# SCK_DATA_BOARD_2_3.net
KiCad netlist of a schematic drawn in EAGLE
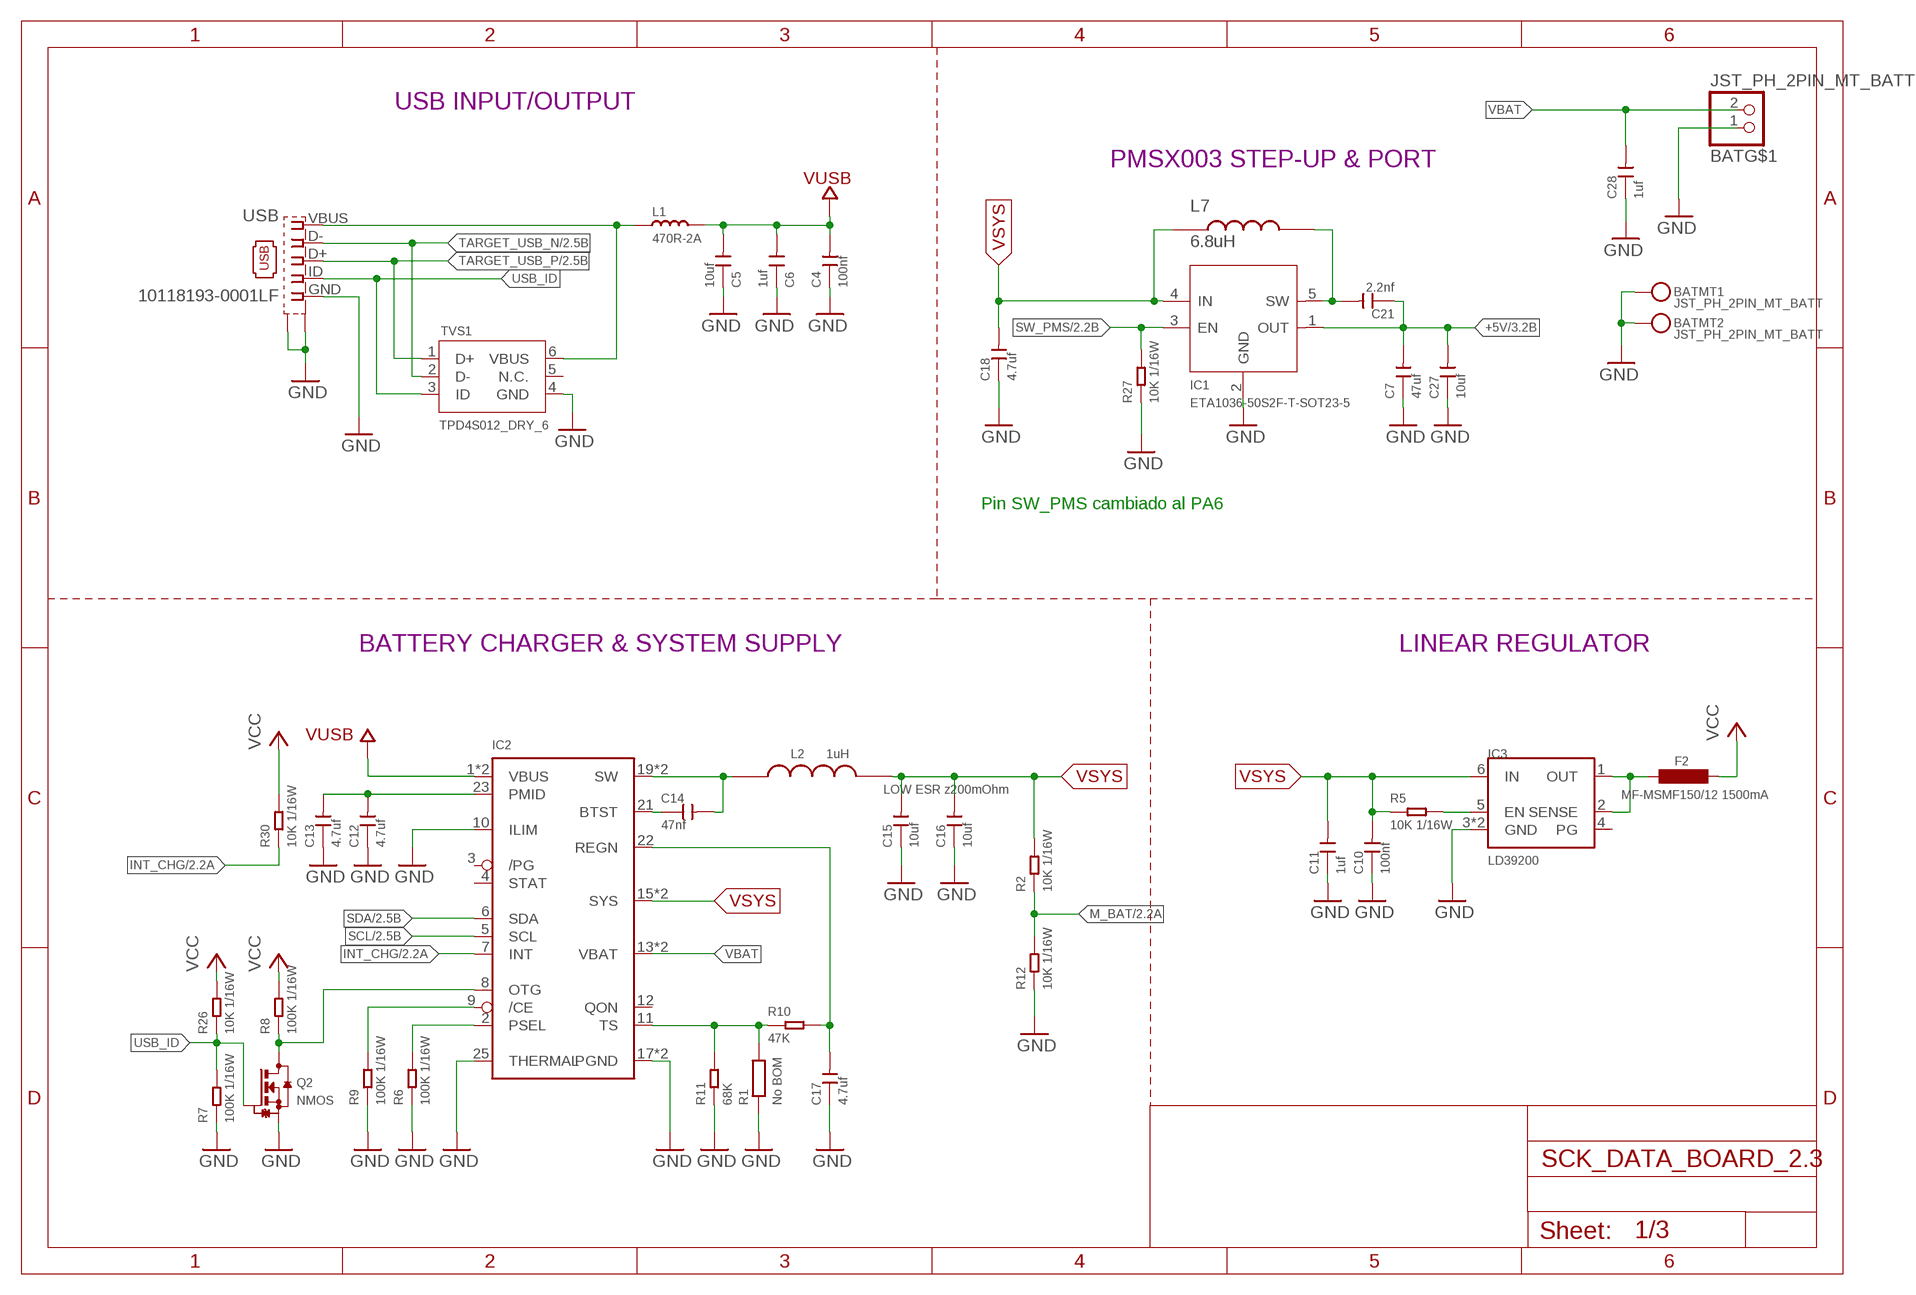
[diagram p0: schematic, sheet 1]
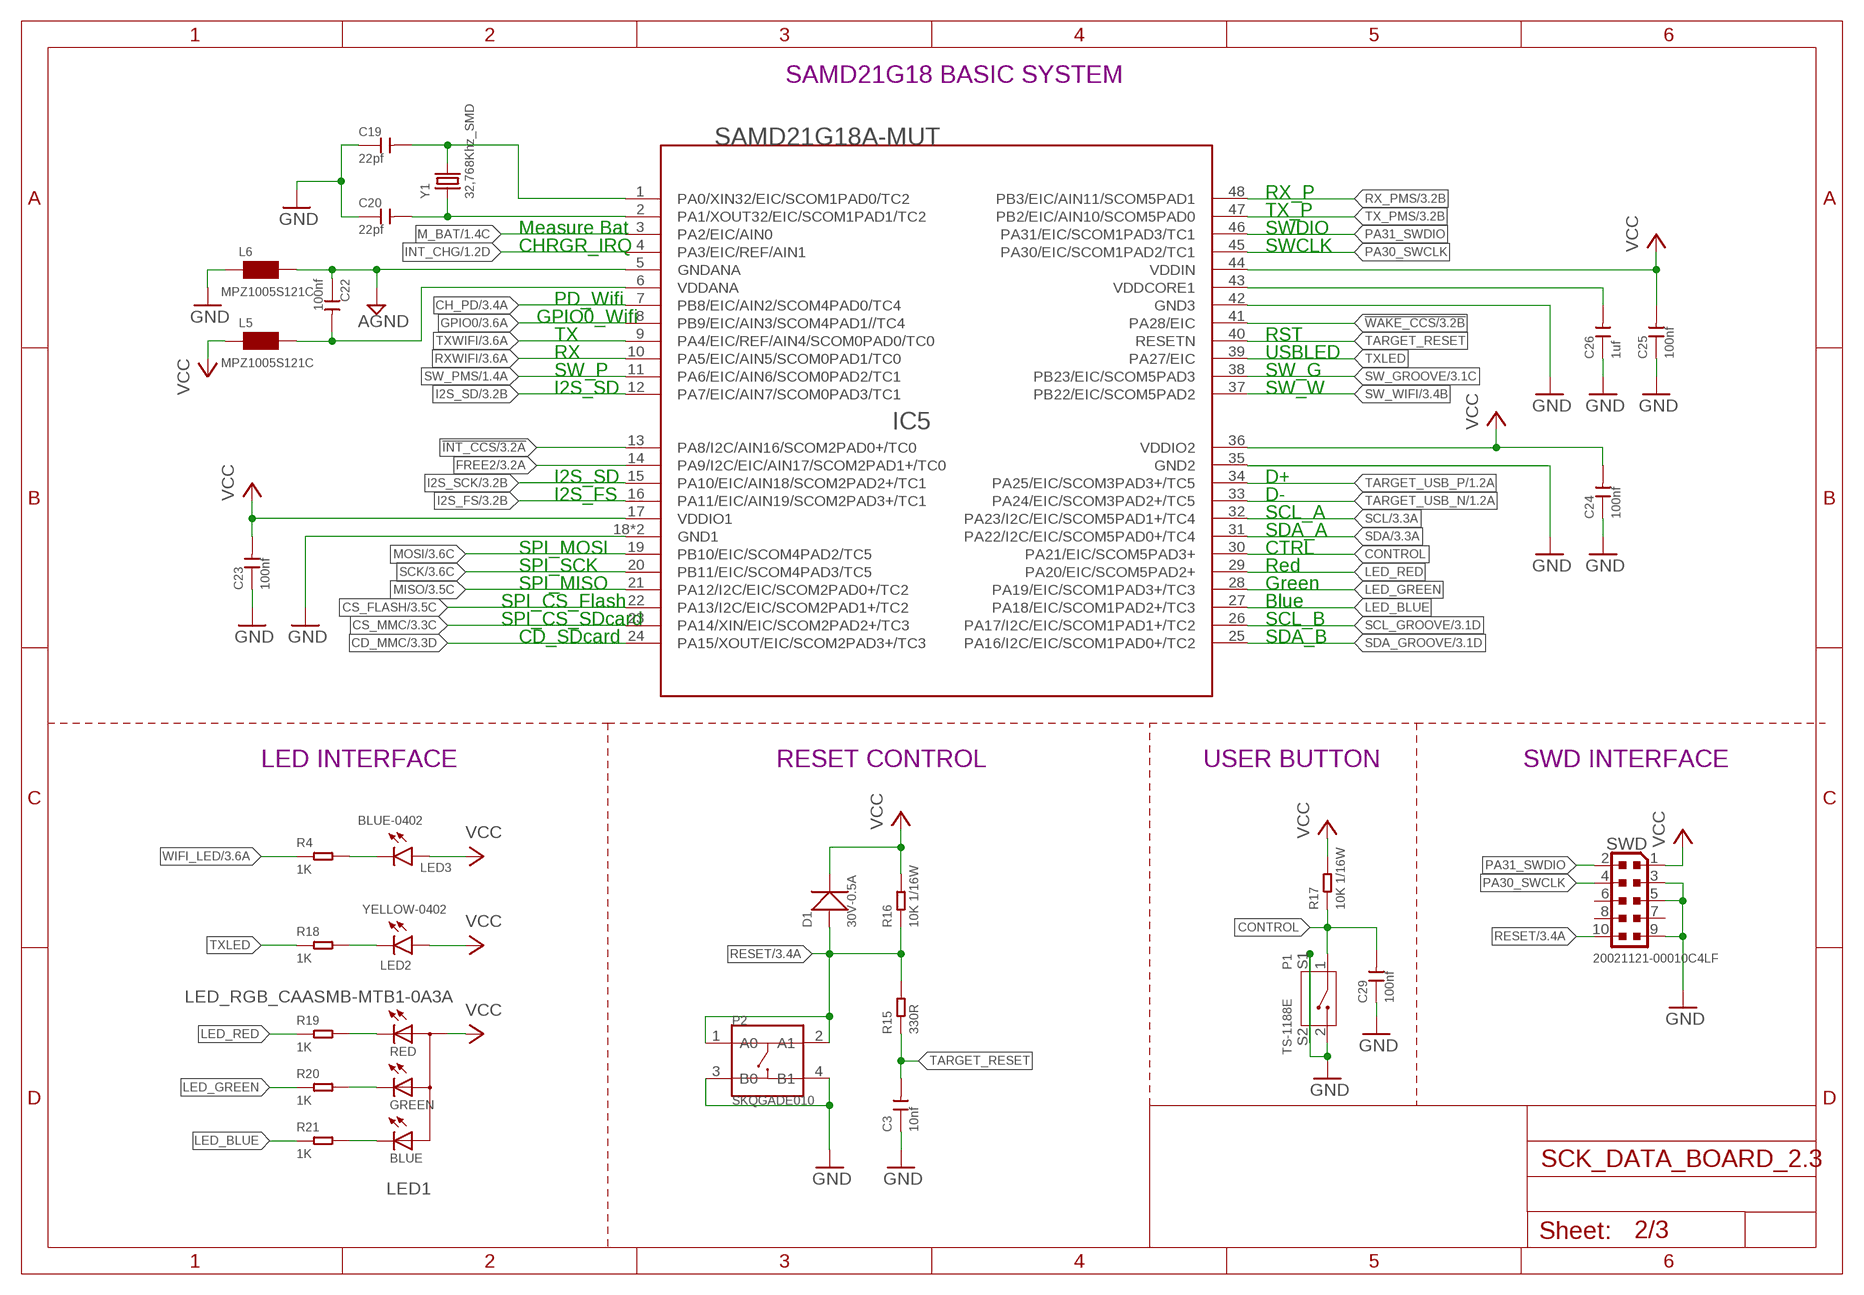
[diagram p1: schematic, sheet 2]
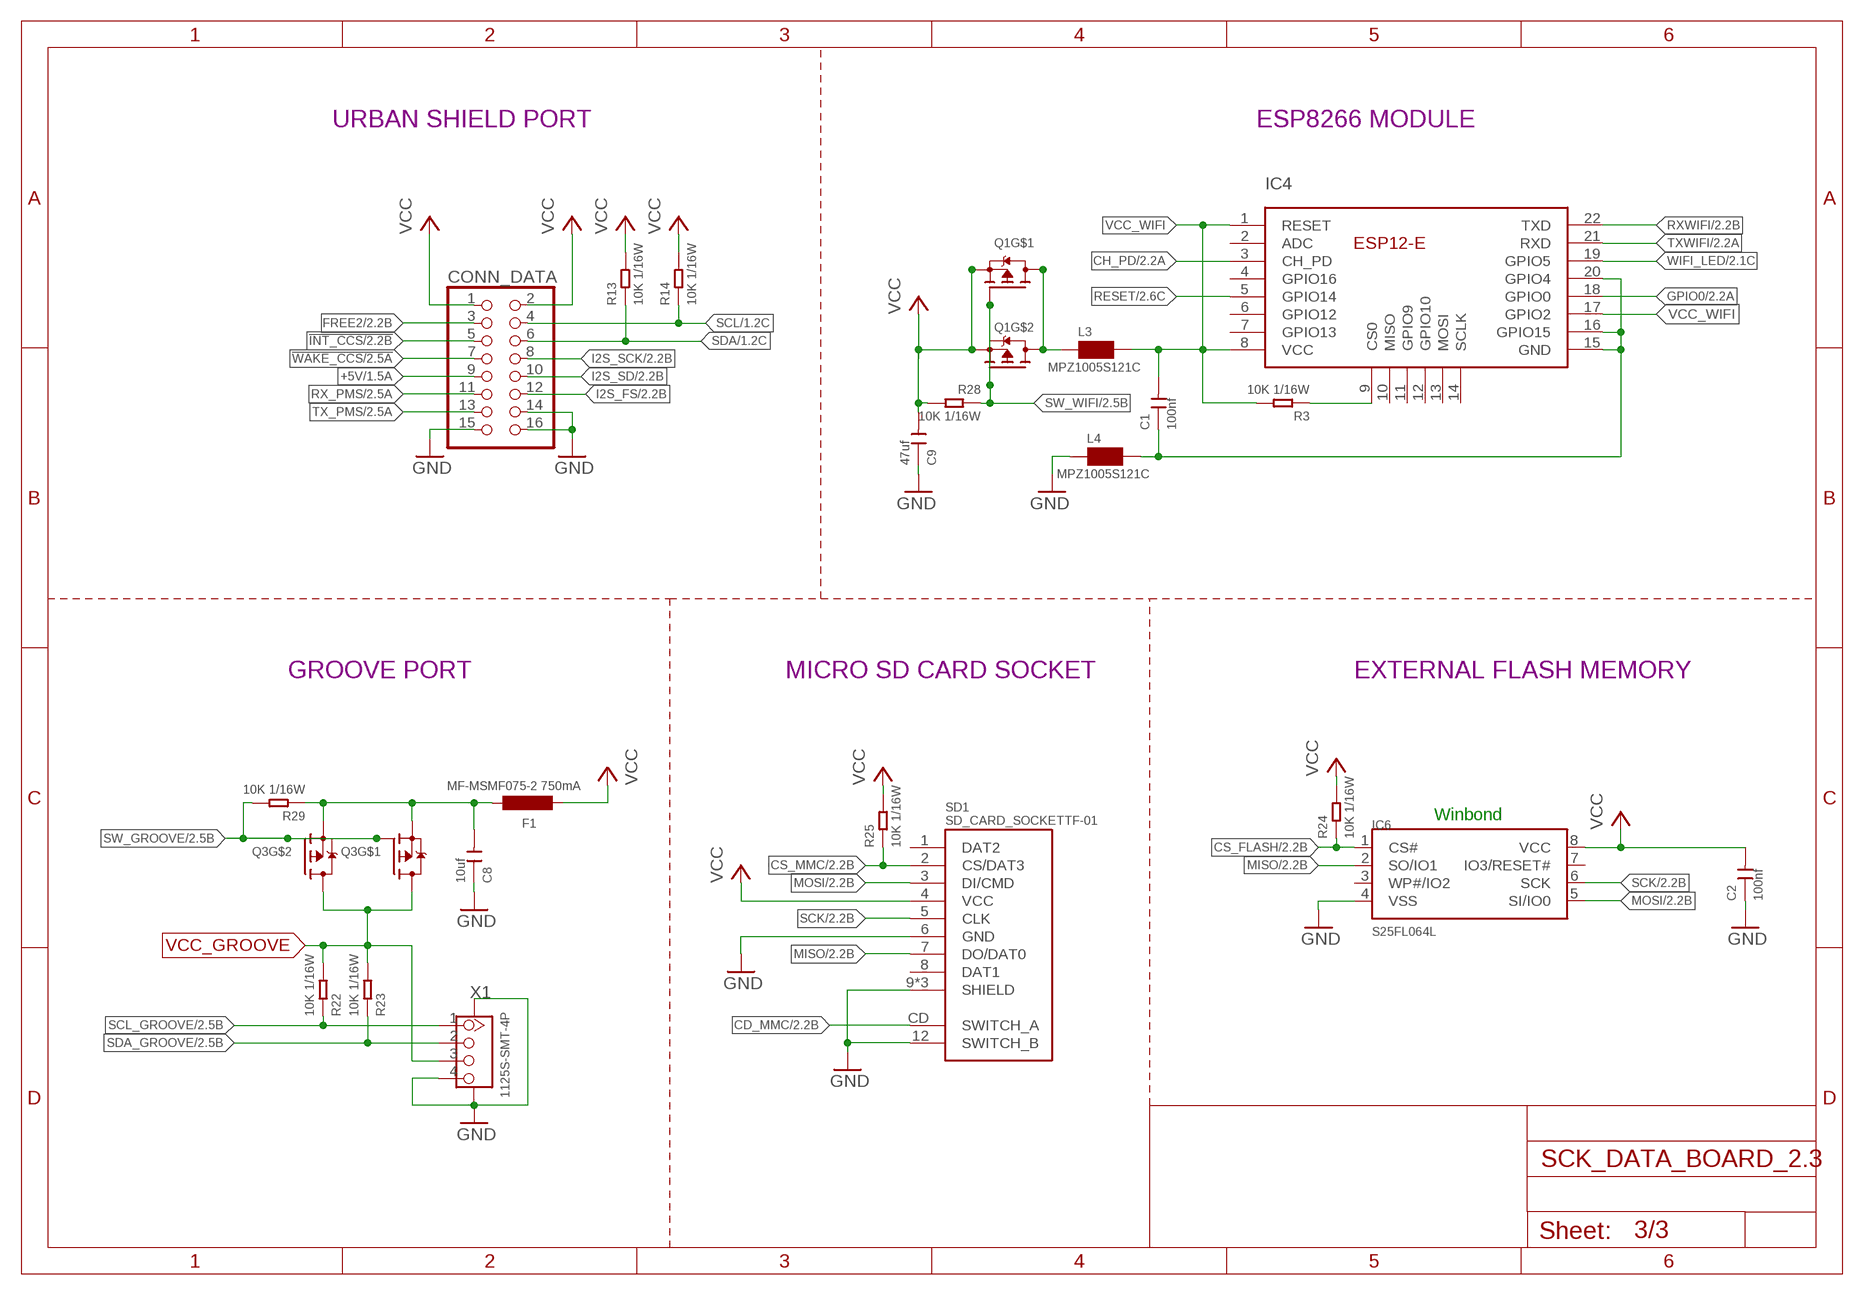
[diagram p2: schematic, sheet 3]

(export (version "E")
  (design (tool "Eeschema 10.0.6"))
  (components
    (comp (ref "C1")
      (value "100nf")
      (footprint "eagle-import:C0402")
      (fields (field (name "MPN") "CC0402KRX7R8BB104"))
      (libsource (lib "eagle-import") (part "CERAMIC-100NF-25V-10%-X7R(0402)"))
    )
    (comp (ref "C2")
      (value "100nf")
      (footprint "eagle-import:C0402")
      (fields (field (name "MPN") "CC0402KRX7R8BB104"))
      (libsource (lib "eagle-import") (part "CERAMIC-100NF-25V-10%-X7R(0402)"))
    )
    (comp (ref "C8")
      (value "10uf")
      (footprint "eagle-import:C1206")
      (fields (field (name "MPN") "CC1206KKX5R8BB106"))
      (libsource (lib "eagle-import") (part "CERAMIC-10UF-25V-10%-X5R(1206)"))
    )
    (comp (ref "C9")
      (value "47uf")
      (footprint "eagle-import:C1210")
      (fields (field (name "MPN") "GRM32ER71A476ME15L"))
      (libsource (lib "eagle-import") (part "CERAMIC-47UF-10V-20%-X7R(1210)"))
    )
    (comp (ref "CONN_DATA")
      (value "PINHD_2X8FEM_SMD")
      (footprint "eagle-import:PINHD_2X8_SMD_FEMALE_UNHOLED")
      (libsource (lib "eagle-import") (part "PINHD_2X8FEM_SMD"))
    )
    (comp (ref "F1")
      (value "MF-MSMF075-2 750mA")
      (footprint "eagle-import:L1812")
      (libsource (lib "eagle-import") (part "L-EUL1812"))
    )
    (comp (ref "IC4")
      (value "HANGAR_ESP-12-E")
      (footprint "eagle-import:HANGAR_ESP12-E")
      (libsource (lib "eagle-import") (part "HANGAR_ESP-12-E"))
    )
    (comp (ref "IC6")
      (value "S25FL064L")
      (footprint "eagle-import:SOIC_8-208MILS")
      (libsource (lib "eagle-import") (part "FLASH_S25FL064L"))
    )
    (comp (ref "L3")
      (value "MPZ1005S121C")
      (footprint "eagle-import:0402")
      (libsource (lib "eagle-import") (part "WE-CBF_0402"))
    )
    (comp (ref "L4")
      (value "MPZ1005S121C")
      (footprint "eagle-import:0402")
      (libsource (lib "eagle-import") (part "WE-CBF_0402"))
    )
    (comp (ref "Q1")
      (value "PMOS")
      (footprint "eagle-import:POWERPAK-SC70-6L")
      (fields (field (name "MPN") "SIA923AEDJ-T1-GE3 "))
      (libsource (lib "eagle-import") (part "MOSFET-PCHANNEL-DUAL"))
    )
    (comp (ref "Q3")
      (value "PMOS")
      (footprint "eagle-import:POWERPAK-SC70-6L")
      (libsource (lib "eagle-import") (part "MOSFET-PCHANNEL-DUAL"))
    )
    (comp (ref "R3")
      (value "10K 1/16W")
      (footprint "eagle-import:R0402")
      (fields (field (name "MPN") "RC0402FR-0710KL"))
      (libsource (lib "eagle-import") (part "SMD-RES-10K-1%-1/16W(0402)"))
    )
    (comp (ref "R13")
      (value "10K 1/16W")
      (footprint "eagle-import:R0402")
      (fields (field (name "MPN") "RC0402FR-0710KL"))
      (libsource (lib "eagle-import") (part "SMD-RES-10K-1%-1/16W(0402)"))
    )
    (comp (ref "R14")
      (value "10K 1/16W")
      (footprint "eagle-import:R0402")
      (fields (field (name "MPN") "RC0402FR-0710KL"))
      (libsource (lib "eagle-import") (part "SMD-RES-10K-1%-1/16W(0402)"))
    )
    (comp (ref "R22")
      (value "10K 1/16W")
      (footprint "eagle-import:R0402")
      (fields (field (name "MPN") "RC0402FR-0710KL"))
      (libsource (lib "eagle-import") (part "SMD-RES-10K-1%-1/16W(0402)"))
    )
    (comp (ref "R23")
      (value "10K 1/16W")
      (footprint "eagle-import:R0402")
      (fields (field (name "MPN") "RC0402FR-0710KL"))
      (libsource (lib "eagle-import") (part "SMD-RES-10K-1%-1/16W(0402)"))
    )
    (comp (ref "R24")
      (value "10K 1/16W")
      (footprint "eagle-import:R0402")
      (fields (field (name "MPN") "RC0402FR-0710KL"))
      (libsource (lib "eagle-import") (part "SMD-RES-10K-1%-1/16W(0402)"))
    )
    (comp (ref "R25")
      (value "10K 1/16W")
      (footprint "eagle-import:R0402")
      (fields (field (name "MPN") "RC0402FR-0710KL"))
      (libsource (lib "eagle-import") (part "SMD-RES-10K-1%-1/16W(0402)"))
    )
    (comp (ref "R28")
      (value "10K 1/16W")
      (footprint "eagle-import:R0402")
      (fields (field (name "MPN") "RC0402FR-0710KL"))
      (libsource (lib "eagle-import") (part "Seeed-Resistor_SMD-RES-10K-1%-1/16W(0402)"))
    )
    (comp (ref "R29")
      (value "10K 1/16W")
      (footprint "eagle-import:R0402")
      (fields (field (name "MPN") "RC0402FR-0710KL"))
      (libsource (lib "eagle-import") (part "Seeed-Resistor_SMD-RES-10K-1%-1/16W(0402)"))
    )
    (comp (ref "SD1")
      (value "SD_CARD_SOCKETTF-01")
      (footprint "eagle-import:TF-01")
      (fields (field (name "MPN") "320090008"))
      (libsource (lib "eagle-import") (part "SD_CARD_SOCKETTF-01"))
    )
    (comp (ref "X1")
      (value "1125S-SMT-4P")
      (footprint "eagle-import:CONNECTOR-NEW_HW4-SMD-2.0")
      (fields (field (name "MPN") "320110030"))
      (libsource (lib "eagle-import") (part "GROVE-CONNECTOR-SMDDD"))
    )
    (comp (ref "BAT")
      (value "JST_PH_2PIN_MT_BATT")
      (footprint "eagle-import:JSTPH2_BATT")
      (libsource (lib "eagle-import") (part "JST_PH_2PIN_MT_BATT"))
    )
    (comp (ref "C4")
      (value "100nf")
      (footprint "eagle-import:C0402")
      (fields (field (name "MPN") "CC0402KRX7R8BB104"))
      (libsource (lib "eagle-import") (part "CERAMIC-100NF-25V-10%-X7R(0402)"))
    )
    (comp (ref "C5")
      (value "10uf")
      (footprint "eagle-import:C1206")
      (fields (field (name "MPN") "CC1206KKX5R8BB106"))
      (libsource (lib "eagle-import") (part "CERAMIC-10UF-25V-10%-X5R(1206)"))
    )
    (comp (ref "C6")
      (value "1uf")
      (footprint "eagle-import:C0805")
      (fields (field (name "MPN") "CC0805KKX7R8BB105"))
      (libsource (lib "eagle-import") (part "CERAMIC-1UF-25V-10%-X7R(0805)"))
    )
    (comp (ref "C7")
      (value "47uf")
      (footprint "eagle-import:C0805")
      (fields (field (name "MPN") "CC0805MKX5R5BB476"))
      (libsource (lib "eagle-import") (part "CERAMIC-47UF-6.3V-20%-X5R(0805)"))
    )
    (comp (ref "C10")
      (value "100nf")
      (footprint "eagle-import:C0402")
      (fields (field (name "MPN") "CC0402KRX7R8BB104"))
      (libsource (lib "eagle-import") (part "CERAMIC-100NF-25V-10%-X7R(0402)"))
    )
    (comp (ref "C11")
      (value "1uf")
      (footprint "eagle-import:C0805")
      (fields (field (name "MPN") "CC0805KKX7R8BB105"))
      (libsource (lib "eagle-import") (part "CERAMIC-1UF-25V-10%-X7R(0805)"))
    )
    (comp (ref "C12")
      (value "4.7uf")
      (footprint "eagle-import:C0603")
      (fields (field (name "MPN") "CC0603KRX5R6BB475"))
      (libsource (lib "eagle-import") (part "CERAMIC-4.7UF-10V-10%-X5R(0603)"))
    )
    (comp (ref "C13")
      (value "4.7uf")
      (footprint "eagle-import:C0603")
      (fields (field (name "MPN") "CC0603KRX5R6BB475"))
      (libsource (lib "eagle-import") (part "CERAMIC-4.7UF-10V-10%-X5R(0603)"))
    )
    (comp (ref "C14")
      (value "47nf")
      (footprint "eagle-import:C0402")
      (fields (field (name "MPN") "CC0402KRX7R8BB473"))
      (libsource (lib "eagle-import") (part "CERAMIC-47NF-25V-10%-X7R(0402)"))
    )
    (comp (ref "C15")
      (value "10uf")
      (footprint "eagle-import:C0603")
      (fields (field (name "MPN") "CC0603KRX5R6BB106"))
      (libsource (lib "eagle-import") (part "Seeed-OPL-Capacitor_CERAMIC-10UF-10V-10%-X5R(0603)"))
    )
    (comp (ref "C16")
      (value "10uf")
      (footprint "eagle-import:C0603")
      (fields (field (name "MPN") "CC0603KRX5R6BB106"))
      (libsource (lib "eagle-import") (part "Seeed-OPL-Capacitor_CERAMIC-10UF-10V-10%-X5R(0603)"))
    )
    (comp (ref "C17")
      (value "4.7uf")
      (footprint "eagle-import:C0603")
      (fields (field (name "MPN") "CC0603KRX5R6BB475"))
      (libsource (lib "eagle-import") (part "CERAMIC-4.7UF-10V-10%-X5R(0603)"))
    )
    (comp (ref "C18")
      (value "4.7uf")
      (footprint "eagle-import:C0603")
      (fields (field (name "MPN") "CC0603KRX5R6BB475"))
      (libsource (lib "eagle-import") (part "CERAMIC-4.7UF-10V-10%-X5R(0603)"))
    )
    (comp (ref "C21")
      (value "2.2nf")
      (footprint "eagle-import:C0402")
      (fields (field (name "MPN") "CC0402KRX7R9BB222"))
      (libsource (lib "eagle-import") (part "CERAMIC-2.2NF-50V-10%-X7R(0402)"))
    )
    (comp (ref "C27")
      (value "10uf")
      (footprint "eagle-import:C0603")
      (fields (field (name "MPN") "CC0603KRX5R6BB106"))
      (libsource (lib "eagle-import") (part "CERAMIC-10UF-10V-10%-X5R(0603)"))
    )
    (comp (ref "C28")
      (value "1uf")
      (footprint "eagle-import:C0805")
      (fields (field (name "MPN") "CC0805KKX7R8BB105"))
      (libsource (lib "eagle-import") (part "CERAMIC-1UF-25V-10%-X7R(0805)"))
    )
    (comp (ref "F2")
      (value "MF-MSMF150/12 1500mA")
      (footprint "eagle-import:L1812")
      (libsource (lib "eagle-import") (part "L-EUL1812"))
    )
    (comp (ref "IC1")
      (value "ETA1036-50S2F-T-SOT23-5")
      (footprint "eagle-import:SOT-23-5")
      (fields (field (name "MPN") "ETA1036-50S2F-T"))
      (libsource (lib "eagle-import") (part "PMIC-ETA1036-50S2F-T(SOT23-5)"))
    )
    (comp (ref "IC2")
      (value "BQ24259_VQFN(24)")
      (footprint "eagle-import:24-PIN_VQFN_THPAD")
      (libsource (lib "eagle-import") (part "BQ24259_VQFN(24)"))
    )
    (comp (ref "IC3")
      (value "LD39200")
      (footprint "eagle-import:DFN6_3X3MM")
      (libsource (lib "eagle-import") (part "LD39200"))
    )
    (comp (ref "L1")
      (value "470R-2A")
      (footprint "eagle-import:L0805")
      (fields (field (name "MPN") "WLB2012-471T20"))
      (libsource (lib "eagle-import") (part "SMD-FERRITE-BEAD-470R-2A(0805)'0805'"))
    )
    (comp (ref "L2")
      (value "1uH")
      (footprint "eagle-import:HANGAR_C1210")
      (libsource (lib "eagle-import") (part "LQH32PN1R0NNCL"))
    )
    (comp (ref "L7")
      (value "6.8uH")
      (footprint "eagle-import:IND_BOURNS_SRN3015TA_3X3_SMD")
      (libsource (lib "eagle-import") (part "RCL_L_SMD_SRN3015TA-6R8M"))
    )
    (comp (ref "Q2")
      (value "NMOS")
      (footprint "eagle-import:NMOS_UMT3")
      (libsource (lib "eagle-import") (part "NMOS_RJU003N03FRAT106"))
    )
    (comp (ref "R1")
      (value "No BOM")
      (footprint "eagle-import:HANGAR_R0402")
      (libsource (lib "eagle-import") (part "HANGAR_R-EU_R0402"))
    )
    (comp (ref "R2")
      (value "10K 1/16W")
      (footprint "eagle-import:R0402")
      (fields (field (name "MPN") "RC0402FR-0710KL"))
      (libsource (lib "eagle-import") (part "SMD-RES-10K-1%-1/16W(0402)"))
    )
    (comp (ref "R5")
      (value "10K 1/16W")
      (footprint "eagle-import:R0402")
      (fields (field (name "MPN") "RC0402FR-0710KL"))
      (libsource (lib "eagle-import") (part "SMD-RES-10K-1%-1/16W(0402)"))
    )
    (comp (ref "R6")
      (value "100K 1/16W")
      (footprint "eagle-import:R0402")
      (fields (field (name "MPN") "RC0402JR-07100KL"))
      (libsource (lib "eagle-import") (part "SMD-RES-100K-5%-1/16W(0402)"))
    )
    (comp (ref "R7")
      (value "100K 1/16W")
      (footprint "eagle-import:R0402")
      (fields (field (name "MPN") "RC0402JR-07100KL"))
      (libsource (lib "eagle-import") (part "SMD-RES-100K-5%-1/16W(0402)"))
    )
    (comp (ref "R8")
      (value "100K 1/16W")
      (footprint "eagle-import:R0402")
      (fields (field (name "MPN") "RC0402JR-07100KL"))
      (libsource (lib "eagle-import") (part "SMD-RES-100K-5%-1/16W(0402)"))
    )
    (comp (ref "R9")
      (value "100K 1/16W")
      (footprint "eagle-import:R0402")
      (fields (field (name "MPN") "RC0402JR-07100KL"))
      (libsource (lib "eagle-import") (part "SMD-RES-100K-5%-1/16W(0402)"))
    )
    (comp (ref "R10")
      (value "47K")
      (footprint "eagle-import:R0402")
      (fields (field (name "MPN") "RC0402JR-0747KL"))
      (libsource (lib "eagle-import") (part "SMD-RES-47K-5%-1/16W(0402)"))
    )
    (comp (ref "R11")
      (value "68K")
      (footprint "eagle-import:R0402")
      (fields (field (name "MPN") "RC0402JR-0768KL"))
      (libsource (lib "eagle-import") (part "SMD-RES-68K-50V-5%(0402)"))
    )
    (comp (ref "R12")
      (value "10K 1/16W")
      (footprint "eagle-import:R0402")
      (fields (field (name "MPN") "RC0402FR-0710KL"))
      (libsource (lib "eagle-import") (part "SMD-RES-10K-1%-1/16W(0402)"))
    )
    (comp (ref "R26")
      (value "10K 1/16W")
      (footprint "eagle-import:R0402")
      (fields (field (name "MPN") "RC0402FR-0710KL"))
      (libsource (lib "eagle-import") (part "SMD-RES-10K-1%-1/16W(0402)"))
    )
    (comp (ref "R27")
      (value "10K 1/16W")
      (footprint "eagle-import:R0402")
      (fields (field (name "MPN") "RC0402FR-0710KL"))
      (libsource (lib "eagle-import") (part "Seeed-Resistor_SMD-RES-10K-1%-1/16W(0402)"))
    )
    (comp (ref "R30")
      (value "10K 1/16W")
      (footprint "eagle-import:R0402")
      (fields (field (name "MPN") "RC0402FR-0710KL"))
      (libsource (lib "eagle-import") (part "SMD-RES-10K-1%-1/16W(0402)"))
    )
    (comp (ref "TVS1")
      (value "TPD4S012_DRY_6")
      (footprint "eagle-import:DRY6")
      (libsource (lib "eagle-import") (part "TPD4S012_DRY_6"))
    )
    (comp (ref "USB")
      (value "10118193-0001LF")
      (footprint "eagle-import:CON2_USB_MICRO_B_AT")
      (libsource (lib "eagle-import") (part "USB_MICRO_USB"))
    )
    (comp (ref "C3")
      (value "10nf")
      (footprint "eagle-import:C0402")
      (fields (field (name "MPN") "CC0402KRX7R9BB103"))
      (libsource (lib "eagle-import") (part "CERAMIC-10NF-50V-10%-X7R(0402)"))
    )
    (comp (ref "C19")
      (value "22pf")
      (footprint "eagle-import:C0402")
      (fields (field (name "MPN") "CC0402JRNPO9BN220"))
      (libsource (lib "eagle-import") (part "CERAMIC-22PF-50V-5%-NPO(0402)"))
    )
    (comp (ref "C20")
      (value "22pf")
      (footprint "eagle-import:C0402")
      (fields (field (name "MPN") "CC0402JRNPO9BN220"))
      (libsource (lib "eagle-import") (part "CERAMIC-22PF-50V-5%-NPO(0402)"))
    )
    (comp (ref "C22")
      (value "100nf")
      (footprint "eagle-import:C0402")
      (fields (field (name "MPN") "CC0402KRX7R8BB104"))
      (libsource (lib "eagle-import") (part "CERAMIC-100NF-25V-10%-X7R(0402)"))
    )
    (comp (ref "C23")
      (value "100nf")
      (footprint "eagle-import:C0402")
      (fields (field (name "MPN") "CC0402KRX7R8BB104"))
      (libsource (lib "eagle-import") (part "CERAMIC-100NF-25V-10%-X7R(0402)"))
    )
    (comp (ref "C24")
      (value "100nf")
      (footprint "eagle-import:C0402")
      (fields (field (name "MPN") "CC0402KRX7R8BB104"))
      (libsource (lib "eagle-import") (part "CERAMIC-100NF-25V-10%-X7R(0402)"))
    )
    (comp (ref "C25")
      (value "100nf")
      (footprint "eagle-import:C0402")
      (fields (field (name "MPN") "CC0402KRX7R8BB104"))
      (libsource (lib "eagle-import") (part "CERAMIC-100NF-25V-10%-X7R(0402)"))
    )
    (comp (ref "C26")
      (value "1uf")
      (footprint "eagle-import:C0805")
      (fields (field (name "MPN") "CC0805KKX7R8BB105"))
      (libsource (lib "eagle-import") (part "CERAMIC-1UF-25V-10%-X7R(0805)"))
    )
    (comp (ref "C29")
      (value "100nf")
      (footprint "eagle-import:C0402")
      (fields (field (name "MPN") "CC0402KRX7R8BB104"))
      (libsource (lib "eagle-import") (part "CERAMIC-100NF-25V-10%-X7R(0402)"))
    )
    (comp (ref "D1")
      (value "30V-0.5A")
      (footprint "eagle-import:SOD-323")
      (fields (field (name "MPN") "LRB551V-30T1G"))
      (libsource (lib "eagle-import") (part "SMD-DIODE-SCHOTTKY-30V-0.5A(SOD-323)"))
    )
    (comp (ref "IC5")
      (value "SAMD21G18A-MUT")
      (footprint "eagle-import:QFN48-7X7")
      (libsource (lib "eagle-import") (part "SAMD21G18A-MUT"))
    )
    (comp (ref "L5")
      (value "MPZ1005S121C")
      (footprint "eagle-import:0402")
      (libsource (lib "eagle-import") (part "WE-CBF_0402"))
    )
    (comp (ref "L6")
      (value "MPZ1005S121C")
      (footprint "eagle-import:0402")
      (libsource (lib "eagle-import") (part "WE-CBF_0402"))
    )
    (comp (ref "LED1")
      (value "LED_RGB_CAASMB-MTB1-0A3A")
      (footprint "eagle-import:HANGAR_P-LCC-4")
      (libsource (lib "eagle-import") (part "LED_RGB_CAASMB-MTB1-0A3A"))
    )
    (comp (ref "LED2")
      (value "YELLOW-0402")
      (footprint "eagle-import:CHIPLED_0402_YELLOW")
      (libsource (lib "eagle-import") (part "Hangar3D_37241589_LEDCHIPLED_0402_YELLOW"))
    )
    (comp (ref "LED3")
      (value "BLUE-0402")
      (footprint "eagle-import:CHIPLED_0402_BLUE")
      (libsource (lib "eagle-import") (part "LEDCHIPLED_0402_BLUE"))
    )
    (comp (ref "P1")
      (value "TS-1188E")
      (footprint "eagle-import:SW4-SMD-7.0X3.5X3.5MM-90D")
      (libsource (lib "eagle-import") (part "SMD-BUTTON(2+2P-7X3.5MM-90D)"))
    )
    (comp (ref "P2")
      (value "SKQGADE010")
      (footprint "eagle-import:SW4-SMD-5.2X5.2X1.5MM")
      (libsource (lib "eagle-import") (part "SKQGADE010-SKQGADE010"))
    )
    (comp (ref "R4")
      (value "1K")
      (footprint "eagle-import:R0402")
      (fields (field (name "MPN") "RC0402JR-071KL"))
      (libsource (lib "eagle-import") (part "SMD-RES-1K-5%-1/16W(0402)"))
    )
    (comp (ref "R15")
      (value "330R")
      (footprint "eagle-import:R0402")
      (fields (field (name "MPN") "RC0402FR-07330RL"))
      (libsource (lib "eagle-import") (part "SMD-RES-330R-1%-1/16W(0402)"))
    )
    (comp (ref "R16")
      (value "10K 1/16W")
      (footprint "eagle-import:R0402")
      (fields (field (name "MPN") "RC0402FR-0710KL"))
      (libsource (lib "eagle-import") (part "SMD-RES-10K-1%-1/16W(0402)"))
    )
    (comp (ref "R17")
      (value "10K 1/16W")
      (footprint "eagle-import:R0402")
      (fields (field (name "MPN") "RC0402FR-0710KL"))
      (libsource (lib "eagle-import") (part "SMD-RES-10K-1%-1/16W(0402)"))
    )
    (comp (ref "R18")
      (value "1K")
      (footprint "eagle-import:R0402")
      (fields (field (name "MPN") "RC0402JR-071KL"))
      (libsource (lib "eagle-import") (part "SMD-RES-1K-5%-1/16W(0402)"))
    )
    (comp (ref "R19")
      (value "1K")
      (footprint "eagle-import:R0402")
      (fields (field (name "MPN") "RC0402JR-071KL"))
      (libsource (lib "eagle-import") (part "SMD-RES-1K-5%-1/16W(0402)"))
    )
    (comp (ref "R20")
      (value "1K")
      (footprint "eagle-import:R0402")
      (fields (field (name "MPN") "RC0402JR-071KL"))
      (libsource (lib "eagle-import") (part "SMD-RES-1K-5%-1/16W(0402)"))
    )
    (comp (ref "R21")
      (value "1K")
      (footprint "eagle-import:R0402")
      (fields (field (name "MPN") "RC0402JR-071KL"))
      (libsource (lib "eagle-import") (part "SMD-RES-1K-5%-1/16W(0402)"))
    )
    (comp (ref "SWD")
      (value "20021121-00010C4LF")
      (footprint "eagle-import:2X05_SMD_1.27MM")
      (libsource (lib "eagle-import") (part "PINHEAD_PINHD-2X5SMD"))
    )
    (comp (ref "Y1")
      (value "32,768Khz_SMD")
      (footprint "eagle-import:CRISTALLI_RESONATOR_EPSON_FC_145")
      (fields (field (name "PART_NUMBER") "ABS07-32.768KHZ-T"))
      (libsource (lib "eagle-import") (part "CRISTALLI_0213_ABS07-32.768KHZ-T"))
    )
  )
  (nets
    (net (code "1") (name "+5V") (class "Default")
      (node (ref "C21") (pin "1") (pinfunction "1_1") (pintype "passive"))
      (node (ref "C27") (pin "2") (pinfunction "2_2") (pintype "passive"))
      (node (ref "C7") (pin "2") (pinfunction "2_2") (pintype "passive"))
      (node (ref "CONN_DATA") (pin "9") (pinfunction "9_9") (pintype "passive"))
      (node (ref "IC1") (pin "1") (pinfunction "OUT_1") (pintype "bidirectional"))
    )
    (net (code "2") (name "AGND") (class "Default")
      (node (ref "C22") (pin "1") (pinfunction "1_1") (pintype "passive"))
      (node (ref "IC5") (pin "5") (pinfunction "GNDANA_5") (pintype "power_in"))
      (node (ref "L6") (pin "2") (pinfunction "2_2") (pintype "passive"))
    )
    (net (code "3") (name "CD_MMC") (class "Default")
      (node (ref "IC5") (pin "24") (pinfunction "PA15/XOUT/EIC/SCOM2PAD3+/TC3_24") (pintype "bidirectional"))
      (node (ref "SD1") (pin "CD") (pinfunction "SWITCH_A_CD") (pintype "bidirectional"))
    )
    (net (code "4") (name "CH_PD") (class "Default")
      (node (ref "IC4") (pin "3") (pinfunction "CH_PD_3") (pintype "input"))
      (node (ref "IC5") (pin "7") (pinfunction "PB8/EIC/AIN2/SCOM4PAD0/TC4_7") (pintype "bidirectional"))
    )
    (net (code "5") (name "CONTROL") (class "Default")
      (node (ref "C29") (pin "2") (pinfunction "2_2") (pintype "passive"))
      (node (ref "IC5") (pin "30") (pinfunction "PA21/EIC/SCOM5PAD3+_30") (pintype "bidirectional"))
      (node (ref "P1") (pin "1") (pinfunction "1_1") (pintype "bidirectional"))
      (node (ref "R17") (pin "1") (pinfunction "1_1") (pintype "passive"))
    )
    (net (code "6") (name "CS_FLASH") (class "Default")
      (node (ref "IC5") (pin "22") (pinfunction "PA13/I2C/EIC/SCOM2PAD1+/TC2_22") (pintype "bidirectional"))
      (node (ref "IC6") (pin "1") (pinfunction "CS#_1") (pintype "bidirectional"))
      (node (ref "R24") (pin "1") (pinfunction "1_1") (pintype "passive"))
    )
    (net (code "7") (name "CS_MMC") (class "Default")
      (node (ref "IC5") (pin "23") (pinfunction "PA14/XIN/EIC/SCOM2PAD2+/TC3_23") (pintype "bidirectional"))
      (node (ref "R25") (pin "1") (pinfunction "1_1") (pintype "passive"))
      (node (ref "SD1") (pin "2") (pinfunction "CS/DAT3_2") (pintype "bidirectional"))
    )
    (net (code "8") (name "FREE2") (class "Default")
      (node (ref "CONN_DATA") (pin "3") (pinfunction "3_3") (pintype "passive"))
      (node (ref "IC5") (pin "14") (pinfunction "PA9/I2C/EIC/AIN17/SCOM2PAD1+/TC0_14") (pintype "bidirectional"))
    )
    (net (code "9") (name "GND") (class "Default")
      (node (ref "BAT") (pin "1") (pinfunction "1_1") (pintype "passive"))
      (node (ref "BAT") (pin "NC1") (pinfunction "P$1_NC1") (pintype "bidirectional"))
      (node (ref "BAT") (pin "NC2") (pinfunction "P$1_NC2") (pintype "bidirectional"))
      (node (ref "C10") (pin "1") (pinfunction "1_1") (pintype "passive"))
      (node (ref "C11") (pin "1") (pinfunction "1_1") (pintype "passive"))
      (node (ref "C12") (pin "1") (pinfunction "1_1") (pintype "passive"))
      (node (ref "C13") (pin "1") (pinfunction "1_1") (pintype "passive"))
      (node (ref "C15") (pin "1") (pinfunction "1_1") (pintype "passive"))
      (node (ref "C16") (pin "1") (pinfunction "1_1") (pintype "passive"))
      (node (ref "C17") (pin "1") (pinfunction "1_1") (pintype "passive"))
      (node (ref "C18") (pin "1") (pinfunction "1_1") (pintype "passive"))
      (node (ref "C19") (pin "1") (pinfunction "1_1") (pintype "passive"))
      (node (ref "C2") (pin "1") (pinfunction "1_1") (pintype "passive"))
      (node (ref "C20") (pin "1") (pinfunction "1_1") (pintype "passive"))
      (node (ref "C23") (pin "1") (pinfunction "1_1") (pintype "passive"))
      (node (ref "C24") (pin "1") (pinfunction "1_1") (pintype "passive"))
      (node (ref "C25") (pin "1") (pinfunction "1_1") (pintype "passive"))
      (node (ref "C26") (pin "1") (pinfunction "1_1") (pintype "passive"))
      (node (ref "C27") (pin "1") (pinfunction "1_1") (pintype "passive"))
      (node (ref "C28") (pin "1") (pinfunction "1_1") (pintype "passive"))
      (node (ref "C29") (pin "1") (pinfunction "1_1") (pintype "passive"))
      (node (ref "C3") (pin "1") (pinfunction "1_1") (pintype "passive"))
      (node (ref "C4") (pin "1") (pinfunction "1_1") (pintype "passive"))
      (node (ref "C5") (pin "1") (pinfunction "1_1") (pintype "passive"))
      (node (ref "C6") (pin "1") (pinfunction "1_1") (pintype "passive"))
      (node (ref "C7") (pin "1") (pinfunction "1_1") (pintype "passive"))
      (node (ref "C8") (pin "1") (pinfunction "1_1") (pintype "passive"))
      (node (ref "C9") (pin "1") (pinfunction "1_1") (pintype "passive"))
      (node (ref "CONN_DATA") (pin "14") (pinfunction "14_14") (pintype "passive"))
      (node (ref "CONN_DATA") (pin "15") (pinfunction "15_15") (pintype "passive"))
      (node (ref "CONN_DATA") (pin "16") (pinfunction "16_16") (pintype "passive"))
      (node (ref "IC1") (pin "2") (pinfunction "GND_2") (pintype "bidirectional"))
      (node (ref "IC2") (pin "10") (pinfunction "ILIM_10") (pintype "bidirectional"))
      (node (ref "IC2") (pin "17") (pinfunction "PGND_17") (pintype "bidirectional"))
      (node (ref "IC2") (pin "18") (pinfunction "PGND_18") (pintype "bidirectional"))
      (node (ref "IC2") (pin "25") (pinfunction "THERMAL_25") (pintype "bidirectional"))
      (node (ref "IC3") (pin "3") (pinfunction "GND_3") (pintype "bidirectional"))
      (node (ref "IC3") (pin "7") (pinfunction "GND_7") (pintype "bidirectional"))
      (node (ref "IC5") (pin "18") (pinfunction "GND1_18") (pintype "power_in"))
      (node (ref "IC5") (pin "35") (pinfunction "GND2_35") (pintype "power_in"))
      (node (ref "IC5") (pin "42") (pinfunction "GND3_42") (pintype "power_in"))
      (node (ref "IC5") (pin "TP") (pinfunction "GND1_TP") (pintype "power_in"))
      (node (ref "IC6") (pin "4") (pinfunction "VSS_4") (pintype "bidirectional"))
      (node (ref "L4") (pin "2") (pinfunction "2_2") (pintype "passive"))
      (node (ref "L6") (pin "1") (pinfunction "1_1") (pintype "passive"))
      (node (ref "P1") (pin "2") (pinfunction "2_2") (pintype "bidirectional"))
      (node (ref "P1") (pin "S1") (pinfunction "S1_S1") (pintype "bidirectional"))
      (node (ref "P1") (pin "S2") (pinfunction "S2_S2") (pintype "bidirectional"))
      (node (ref "P2") (pin "3") (pinfunction "B0_3") (pintype "bidirectional"))
      (node (ref "P2") (pin "4") (pinfunction "B1_4") (pintype "bidirectional"))
      (node (ref "Q2") (pin "1") (pinfunction "S_1") (pintype "passive"))
      (node (ref "R1") (pin "1") (pinfunction "1_1") (pintype "passive"))
      (node (ref "R11") (pin "1") (pinfunction "1_1") (pintype "passive"))
      (node (ref "R12") (pin "1") (pinfunction "1_1") (pintype "passive"))
      (node (ref "R27") (pin "1") (pinfunction "1_1") (pintype "passive"))
      (node (ref "R6") (pin "1") (pinfunction "1_1") (pintype "passive"))
      (node (ref "R7") (pin "1") (pinfunction "1_1") (pintype "passive"))
      (node (ref "R9") (pin "1") (pinfunction "1_1") (pintype "passive"))
      (node (ref "SD1") (pin "10") (pinfunction "SHIELD_10") (pintype "bidirectional"))
      (node (ref "SD1") (pin "11") (pinfunction "SHIELD_11") (pintype "bidirectional"))
      (node (ref "SD1") (pin "12") (pinfunction "SWITCH_B_12") (pintype "bidirectional"))
      (node (ref "SD1") (pin "6") (pinfunction "GND_6") (pintype "bidirectional"))
      (node (ref "SD1") (pin "9") (pinfunction "SHIELD_9") (pintype "bidirectional"))
      (node (ref "SWD") (pin "3") (pinfunction "3_3") (pintype "passive"))
      (node (ref "SWD") (pin "5") (pinfunction "5_5") (pintype "passive"))
      (node (ref "SWD") (pin "9") (pinfunction "9_9") (pintype "passive"))
      (node (ref "TVS1") (pin "4") (pinfunction "GND_4") (pintype "passive"))
      (node (ref "USB") (pin "GND") (pinfunction "5_GND") (pintype "passive"))
      (node (ref "USB") (pin "P$1") (pinfunction "S1_P$1") (pintype "passive"))
      (node (ref "USB") (pin "P$2") (pinfunction "S1_P$2") (pintype "passive"))
      (node (ref "USB") (pin "P$3") (pinfunction "S1_P$3") (pintype "passive"))
      (node (ref "USB") (pin "P$4") (pinfunction "S1_P$4") (pintype "passive"))
      (node (ref "USB") (pin "P$5") (pinfunction "S1_P$5") (pintype "passive"))
      (node (ref "USB") (pin "P$6") (pinfunction "S1_P$6") (pintype "passive"))
      (node (ref "USB") (pin "P$7") (pinfunction "S1_P$7") (pintype "passive"))
      (node (ref "USB") (pin "P$8") (pinfunction "S1_P$8") (pintype "passive"))
      (node (ref "USB") (pin "S1") (pinfunction "S2_S1") (pintype "passive"))
      (node (ref "USB") (pin "S2") (pinfunction "S2_S2") (pintype "passive"))
      (node (ref "USB") (pin "S3") (pinfunction "S2_S3") (pintype "passive"))
      (node (ref "USB") (pin "S4") (pinfunction "S2_S4") (pintype "passive"))
      (node (ref "USB") (pin "S5") (pinfunction "S2_S5") (pintype "passive"))
      (node (ref "USB") (pin "S6") (pinfunction "S2_S6") (pintype "passive"))
      (node (ref "X1") (pin "4") (pinfunction "4_4") (pintype "bidirectional"))
      (node (ref "X1") (pin "SS1") (pinfunction "SS1_SS1") (pintype "bidirectional"))
      (node (ref "X1") (pin "SS2") (pinfunction "SS2_SS2") (pintype "bidirectional"))
    )
    (net (code "10") (name "GPIO0") (class "Default")
      (node (ref "IC4") (pin "18") (pinfunction "GPIO0_18") (pintype "bidirectional"))
      (node (ref "IC5") (pin "8") (pinfunction "PB9/EIC/AIN3/SCOM4PAD1//TC4_8") (pintype "bidirectional"))
    )
    (net (code "11") (name "I2S_FS") (class "Default")
      (node (ref "CONN_DATA") (pin "12") (pinfunction "12_12") (pintype "passive"))
      (node (ref "IC5") (pin "16") (pinfunction "PA11/EIC/AIN19/SCOM2PAD3+/TC1_16") (pintype "bidirectional"))
    )
    (net (code "12") (name "I2S_SCK") (class "Default")
      (node (ref "CONN_DATA") (pin "8") (pinfunction "8_8") (pintype "passive"))
      (node (ref "IC5") (pin "15") (pinfunction "PA10/EIC/AIN18/SCOM2PAD2+/TC1_15") (pintype "bidirectional"))
    )
    (net (code "13") (name "I2S_SD") (class "Default")
      (node (ref "CONN_DATA") (pin "10") (pinfunction "10_10") (pintype "passive"))
      (node (ref "IC5") (pin "12") (pinfunction "PA7/EIC/AIN7/SCOM0PAD3/TC1_12") (pintype "bidirectional"))
    )
    (net (code "14") (name "INT_CHG") (class "Default")
      (node (ref "IC2") (pin "7") (pinfunction "INT_7") (pintype "bidirectional"))
      (node (ref "IC5") (pin "4") (pinfunction "PA3/EIC/REF/AIN1_4") (pintype "bidirectional"))
      (node (ref "R30") (pin "1") (pinfunction "1_1") (pintype "passive"))
    )
    (net (code "15") (name "LED_BLUE") (class "Default")
      (node (ref "IC5") (pin "27") (pinfunction "PA18/EIC/SCOM1PAD2+/TC3_27") (pintype "bidirectional"))
      (node (ref "R21") (pin "1") (pinfunction "1_1") (pintype "passive"))
    )
    (net (code "16") (name "LED_GREEN") (class "Default")
      (node (ref "IC5") (pin "28") (pinfunction "PA19/EIC/SCOM1PAD3+/TC3_28") (pintype "bidirectional"))
      (node (ref "R20") (pin "1") (pinfunction "1_1") (pintype "passive"))
    )
    (net (code "17") (name "LED_RED") (class "Default")
      (node (ref "IC5") (pin "29") (pinfunction "PA20/EIC/SCOM5PAD2+_29") (pintype "bidirectional"))
      (node (ref "R19") (pin "1") (pinfunction "1_1") (pintype "passive"))
    )
    (net (code "18") (name "MISO") (class "Default")
      (node (ref "IC5") (pin "21") (pinfunction "PA12/I2C/EIC/SCOM2PAD0+/TC2_21") (pintype "bidirectional"))
      (node (ref "IC6") (pin "2") (pinfunction "SO/IO1_2") (pintype "bidirectional"))
      (node (ref "SD1") (pin "7") (pinfunction "DO/DAT0_7") (pintype "bidirectional"))
    )
    (net (code "19") (name "MOSI") (class "Default")
      (node (ref "IC5") (pin "19") (pinfunction "PB10/EIC/SCOM4PAD2/TC5_19") (pintype "bidirectional"))
      (node (ref "IC6") (pin "5") (pinfunction "SI/IO0_5") (pintype "bidirectional"))
      (node (ref "SD1") (pin "3") (pinfunction "DI/CMD_3") (pintype "bidirectional"))
    )
    (net (code "20") (name "M_BAT") (class "Default")
      (node (ref "IC5") (pin "3") (pinfunction "PA2/EIC/AIN0_3") (pintype "bidirectional"))
      (node (ref "R12") (pin "2") (pinfunction "2_2") (pintype "passive"))
      (node (ref "R2") (pin "1") (pinfunction "1_1") (pintype "passive"))
    )
    (net (code "21") (name "Net-(C14-Pad2)") (class "Default")
      (node (ref "C14") (pin "2") (pinfunction "2_2") (pintype "passive"))
      (node (ref "IC2") (pin "19") (pinfunction "SW_19") (pintype "bidirectional"))
      (node (ref "IC2") (pin "20") (pinfunction "SW_20") (pintype "bidirectional"))
      (node (ref "L2") (pin "1") (pinfunction "1_1") (pintype "bidirectional"))
    )
    (net (code "22") (name "Net-(IC1-SW)") (class "Default")
      (node (ref "C21") (pin "2") (pinfunction "2_2") (pintype "passive"))
      (node (ref "IC1") (pin "5") (pinfunction "SW_5") (pintype "bidirectional"))
      (node (ref "L7") (pin "P$2") (pinfunction "P$2_P$2") (pintype "bidirectional"))
    )
    (net (code "23") (name "Net-(IC2-BTST)") (class "Default")
      (node (ref "C14") (pin "1") (pinfunction "1_1") (pintype "passive"))
      (node (ref "IC2") (pin "21") (pinfunction "BTST_21") (pintype "bidirectional"))
    )
    (net (code "24") (name "Net-(IC2-OTG)") (class "Default")
      (node (ref "IC2") (pin "8") (pinfunction "OTG_8") (pintype "bidirectional"))
      (node (ref "Q2") (pin "3") (pinfunction "D_3") (pintype "passive"))
      (node (ref "R8") (pin "1") (pinfunction "1_1") (pintype "passive"))
    )
    (net (code "25") (name "Net-(IC2-PMID)") (class "Default")
      (node (ref "C12") (pin "2") (pinfunction "2_2") (pintype "passive"))
      (node (ref "C13") (pin "2") (pinfunction "2_2") (pintype "passive"))
      (node (ref "IC2") (pin "23") (pinfunction "PMID_23") (pintype "bidirectional"))
    )
    (net (code "26") (name "Net-(IC2-PSEL)") (class "Default")
      (node (ref "IC2") (pin "2") (pinfunction "PSEL_2") (pintype "bidirectional"))
      (node (ref "R6") (pin "2") (pinfunction "2_2") (pintype "passive"))
    )
    (net (code "27") (name "Net-(IC2-REGN)") (class "Default")
      (node (ref "C17") (pin "2") (pinfunction "2_2") (pintype "passive"))
      (node (ref "IC2") (pin "22") (pinfunction "REGN_22") (pintype "bidirectional"))
      (node (ref "R10") (pin "2") (pinfunction "2_2") (pintype "passive"))
    )
    (net (code "28") (name "Net-(IC2-TS)") (class "Default")
      (node (ref "IC2") (pin "11") (pinfunction "TS_11") (pintype "bidirectional"))
      (node (ref "R1") (pin "2") (pinfunction "2_2") (pintype "passive"))
      (node (ref "R10") (pin "1") (pinfunction "1_1") (pintype "passive"))
      (node (ref "R11") (pin "2") (pinfunction "2_2") (pintype "passive"))
    )
    (net (code "29") (name "Net-(IC2-{slash}CE)") (class "Default")
      (node (ref "IC2") (pin "9") (pinfunction "/CE_9") (pintype "bidirectional"))
      (node (ref "R9") (pin "2") (pinfunction "2_2") (pintype "passive"))
    )
    (net (code "30") (name "Net-(IC3-EN)") (class "Default")
      (node (ref "IC3") (pin "5") (pinfunction "EN_5") (pintype "bidirectional"))
      (node (ref "R5") (pin "2") (pinfunction "2_2") (pintype "passive"))
    )
    (net (code "31") (name "Net-(IC3-OUT)") (class "Default")
      (node (ref "F2") (pin "2") (pinfunction "2_2") (pintype "passive"))
      (node (ref "IC3") (pin "1") (pinfunction "OUT_1") (pintype "bidirectional"))
      (node (ref "IC3") (pin "2") (pinfunction "SENSE_2") (pintype "bidirectional"))
    )
    (net (code "32") (name "Net-(IC4-CS0)") (class "Default")
      (node (ref "IC4") (pin "9") (pinfunction "CS0_9") (pintype "input"))
      (node (ref "R3") (pin "1") (pinfunction "1_1") (pintype "passive"))
    )
    (net (code "33") (name "Net-(IC4-GND)") (class "Default")
      (node (ref "C1") (pin "1") (pinfunction "1_1") (pintype "passive"))
      (node (ref "IC4") (pin "15") (pinfunction "GND_15") (pintype "power_in"))
      (node (ref "IC4") (pin "16") (pinfunction "GPIO15_16") (pintype "bidirectional"))
      (node (ref "IC4") (pin "20") (pinfunction "GPIO4_20") (pintype "bidirectional"))
      (node (ref "L4") (pin "1") (pinfunction "1_1") (pintype "passive"))
    )
    (net (code "34") (name "Net-(IC5-PA0{slash}XIN32{slash}EIC{slash}SCOM1PAD0{slash}TC2)") (class "Default")
      (node (ref "C19") (pin "2") (pinfunction "2_2") (pintype "passive"))
      (node (ref "IC5") (pin "1") (pinfunction "PA0/XIN32/EIC/SCOM1PAD0/TC2_1") (pintype "bidirectional"))
      (node (ref "Y1") (pin "P$2") (pinfunction "2_P$2") (pintype "bidirectional"))
    )
    (net (code "35") (name "Net-(IC5-PA1{slash}XOUT32{slash}EIC{slash}SCOM1PAD1{slash}TC2)") (class "Default")
      (node (ref "C20") (pin "2") (pinfunction "2_2") (pintype "passive"))
      (node (ref "IC5") (pin "2") (pinfunction "PA1/XOUT32/EIC/SCOM1PAD1/TC2_2") (pintype "bidirectional"))
      (node (ref "Y1") (pin "P$1") (pinfunction "1_P$1") (pintype "bidirectional"))
    )
    (net (code "36") (name "Net-(IC5-VDDANA)") (class "Default")
      (node (ref "C22") (pin "2") (pinfunction "2_2") (pintype "passive"))
      (node (ref "IC5") (pin "6") (pinfunction "VDDANA_6") (pintype "power_in"))
      (node (ref "L5") (pin "2") (pinfunction "2_2") (pintype "passive"))
    )
    (net (code "37") (name "Net-(IC5-VDDCORE1)") (class "Default")
      (node (ref "C26") (pin "2") (pinfunction "2_2") (pintype "passive"))
      (node (ref "IC5") (pin "43") (pinfunction "VDDCORE1_43") (pintype "input"))
    )
    (net (code "38") (name "Net-(L3-Pad2)") (class "Default")
      (node (ref "L3") (pin "2") (pinfunction "2_2") (pintype "passive"))
      (node (ref "Q1") (pin "3") (pinfunction "D_3") (pintype "passive"))
      (node (ref "Q1") (pin "6") (pinfunction "D_6") (pintype "passive"))
      (node (ref "Q1") (pin "TP1") (pinfunction "D_TP1") (pintype "passive"))
      (node (ref "Q1") (pin "TP2") (pinfunction "D_TP2") (pintype "passive"))
    )
    (net (code "39") (name "Net-(LED1-BLUE)") (class "Default")
      (node (ref "LED1") (pin "3") (pinfunction "BLUE_3") (pintype "passive"))
      (node (ref "R21") (pin "2") (pinfunction "2_2") (pintype "passive"))
    )
    (net (code "40") (name "Net-(LED1-GREEN)") (class "Default")
      (node (ref "LED1") (pin "2") (pinfunction "GREEN_2") (pintype "passive"))
      (node (ref "R20") (pin "2") (pinfunction "2_2") (pintype "passive"))
    )
    (net (code "41") (name "Net-(LED1-RED)") (class "Default")
      (node (ref "LED1") (pin "1") (pinfunction "RED_1") (pintype "passive"))
      (node (ref "R19") (pin "2") (pinfunction "2_2") (pintype "passive"))
    )
    (net (code "42") (name "Net-(LED2-C)") (class "Default")
      (node (ref "LED2") (pin "K") (pinfunction "C_K") (pintype "passive"))
      (node (ref "R18") (pin "2") (pinfunction "2_2") (pintype "passive"))
    )
    (net (code "43") (name "Net-(LED3-C)") (class "Default")
      (node (ref "LED3") (pin "K") (pinfunction "C_K") (pintype "passive"))
      (node (ref "R4") (pin "2") (pinfunction "2_2") (pintype "passive"))
    )
    (net (code "44") (name "Net-(Q3A-S)") (class "Default")
      (node (ref "C8") (pin "2") (pinfunction "2_2") (pintype "passive"))
      (node (ref "F1") (pin "1") (pinfunction "1_1") (pintype "passive"))
      (node (ref "Q3") (pin "1") (pinfunction "S_1") (pintype "passive"))
      (node (ref "Q3") (pin "4") (pinfunction "S_4") (pintype "passive"))
      (node (ref "R29") (pin "1") (pinfunction "1_1") (pintype "passive"))
    )
    (net (code "45") (name "Net-(TVS1-VBUS)") (class "Default")
      (node (ref "L1") (pin "1") (pinfunction "1_1") (pintype "passive"))
      (node (ref "TVS1") (pin "6") (pinfunction "VBUS_6") (pintype "passive"))
      (node (ref "USB") (pin "VBUS") (pinfunction "1_VBUS") (pintype "passive"))
    )
    (net (code "46") (name "PA30_SWCLK") (class "Default")
      (node (ref "IC5") (pin "45") (pinfunction "PA30/EIC/SCOM1PAD2/TC1_45") (pintype "bidirectional"))
      (node (ref "SWD") (pin "4") (pinfunction "4_4") (pintype "passive"))
    )
    (net (code "47") (name "PA31_SWDIO") (class "Default")
      (node (ref "IC5") (pin "46") (pinfunction "PA31/EIC/SCOM1PAD3/TC1_46") (pintype "bidirectional"))
      (node (ref "SWD") (pin "2") (pinfunction "2_2") (pintype "passive"))
    )
    (net (code "48") (name "RESET") (class "Default")
      (node (ref "D1") (pin "+") (pinfunction "+_+") (pintype "passive"))
      (node (ref "IC4") (pin "5") (pinfunction "GPIO14_5") (pintype "bidirectional"))
      (node (ref "P2") (pin "1") (pinfunction "A0_1") (pintype "bidirectional"))
      (node (ref "P2") (pin "2") (pinfunction "A1_2") (pintype "bidirectional"))
      (node (ref "R15") (pin "2") (pinfunction "2_2") (pintype "passive"))
      (node (ref "R16") (pin "1") (pinfunction "1_1") (pintype "passive"))
      (node (ref "SWD") (pin "10") (pinfunction "10_10") (pintype "passive"))
    )
    (net (code "49") (name "RXWIFI") (class "Default")
      (node (ref "IC4") (pin "22") (pinfunction "TXD_22") (pintype "output"))
      (node (ref "IC5") (pin "10") (pinfunction "PA5/EIC/AIN5/SCOM0PAD1/TC0_10") (pintype "bidirectional"))
    )
    (net (code "50") (name "RX_PMS") (class "Default")
      (node (ref "CONN_DATA") (pin "11") (pinfunction "11_11") (pintype "passive"))
      (node (ref "IC5") (pin "48") (pinfunction "PB3/EIC/AIN11/SCOM5PAD1_48") (pintype "bidirectional"))
    )
    (net (code "51") (name "SCK") (class "Default")
      (node (ref "IC5") (pin "20") (pinfunction "PB11/EIC/SCOM4PAD3/TC5_20") (pintype "bidirectional"))
      (node (ref "IC6") (pin "6") (pinfunction "SCK_6") (pintype "bidirectional"))
      (node (ref "SD1") (pin "5") (pinfunction "CLK_5") (pintype "bidirectional"))
    )
    (net (code "52") (name "SCL") (class "Default")
      (node (ref "CONN_DATA") (pin "4") (pinfunction "4_4") (pintype "passive"))
      (node (ref "IC2") (pin "5") (pinfunction "SCL_5") (pintype "bidirectional"))
      (node (ref "IC5") (pin "32") (pinfunction "PA23/I2C/EIC/SCOM5PAD1+/TC4_32") (pintype "bidirectional"))
      (node (ref "R14") (pin "1") (pinfunction "1_1") (pintype "passive"))
    )
    (net (code "53") (name "SCL_GROOVE") (class "Default")
      (node (ref "IC5") (pin "26") (pinfunction "PA17/I2C/EIC/SCOM1PAD1+/TC2_26") (pintype "bidirectional"))
      (node (ref "R22") (pin "1") (pinfunction "1_1") (pintype "passive"))
      (node (ref "X1") (pin "1") (pinfunction "1_1") (pintype "bidirectional"))
    )
    (net (code "54") (name "SDA") (class "Default")
      (node (ref "CONN_DATA") (pin "6") (pinfunction "6_6") (pintype "passive"))
      (node (ref "IC2") (pin "6") (pinfunction "SDA_6") (pintype "bidirectional"))
      (node (ref "IC5") (pin "31") (pinfunction "PA22/I2C/EIC/SCOM5PAD0+/TC4_31") (pintype "bidirectional"))
      (node (ref "R13") (pin "1") (pinfunction "1_1") (pintype "passive"))
    )
    (net (code "55") (name "SDA_GROOVE") (class "Default")
      (node (ref "IC5") (pin "25") (pinfunction "PA16/I2C/EIC/SCOM1PAD0+/TC2_25") (pintype "bidirectional"))
      (node (ref "R23") (pin "1") (pinfunction "1_1") (pintype "passive"))
      (node (ref "X1") (pin "2") (pinfunction "2_2") (pintype "bidirectional"))
    )
    (net (code "56") (name "SW_GROOVE") (class "Default")
      (node (ref "IC5") (pin "38") (pinfunction "PB23/EIC/SCOM5PAD3_38") (pintype "bidirectional"))
      (node (ref "Q3") (pin "2") (pinfunction "G_2") (pintype "passive"))
      (node (ref "Q3") (pin "5") (pinfunction "G_5") (pintype "passive"))
      (node (ref "R29") (pin "2") (pinfunction "2_2") (pintype "passive"))
    )
    (net (code "57") (name "SW_PMS") (class "Default")
      (node (ref "IC1") (pin "3") (pinfunction "EN_3") (pintype "bidirectional"))
      (node (ref "IC5") (pin "11") (pinfunction "PA6/EIC/AIN6/SCOM0PAD2/TC1_11") (pintype "bidirectional"))
      (node (ref "R27") (pin "2") (pinfunction "2_2") (pintype "passive"))
    )
    (net (code "58") (name "SW_WIFI") (class "Default")
      (node (ref "IC5") (pin "37") (pinfunction "PB22/EIC/SCOM5PAD2_37") (pintype "bidirectional"))
      (node (ref "Q1") (pin "2") (pinfunction "G_2") (pintype "passive"))
      (node (ref "Q1") (pin "5") (pinfunction "G_5") (pintype "passive"))
      (node (ref "R28") (pin "1") (pinfunction "1_1") (pintype "passive"))
    )
    (net (code "59") (name "TARGET_RESET") (class "Default")
      (node (ref "C3") (pin "2") (pinfunction "2_2") (pintype "passive"))
      (node (ref "IC5") (pin "40") (pinfunction "RESETN_40") (pintype "bidirectional"))
      (node (ref "R15") (pin "1") (pinfunction "1_1") (pintype "passive"))
    )
    (net (code "60") (name "TARGET_USB_N") (class "Default")
      (node (ref "IC5") (pin "33") (pinfunction "PA24/EIC/SCOM3PAD2+/TC5_33") (pintype "bidirectional"))
      (node (ref "TVS1") (pin "2") (pinfunction "D-_2") (pintype "passive"))
      (node (ref "USB") (pin "D-") (pinfunction "2_D-") (pintype "passive"))
    )
    (net (code "61") (name "TARGET_USB_P") (class "Default")
      (node (ref "IC5") (pin "34") (pinfunction "PA25/EIC/SCOM3PAD3+/TC5_34") (pintype "bidirectional"))
      (node (ref "TVS1") (pin "1") (pinfunction "D+_1") (pintype "passive"))
      (node (ref "USB") (pin "D+") (pinfunction "3_D+") (pintype "passive"))
    )
    (net (code "62") (name "TXLED") (class "Default")
      (node (ref "IC5") (pin "39") (pinfunction "PA27/EIC_39") (pintype "bidirectional"))
      (node (ref "R18") (pin "1") (pinfunction "1_1") (pintype "passive"))
    )
    (net (code "63") (name "TXWIFI") (class "Default")
      (node (ref "IC4") (pin "21") (pinfunction "RXD_21") (pintype "input"))
      (node (ref "IC5") (pin "9") (pinfunction "PA4/EIC/REF/AIN4/SCOM0PAD0/TC0_9") (pintype "bidirectional"))
    )
    (net (code "64") (name "TX_PMS") (class "Default")
      (node (ref "CONN_DATA") (pin "13") (pinfunction "13_13") (pintype "passive"))
      (node (ref "IC5") (pin "47") (pinfunction "PB2/EIC/AIN10/SCOM5PAD0_47") (pintype "bidirectional"))
    )
    (net (code "65") (name "USB_ID") (class "Default")
      (node (ref "Q2") (pin "2") (pinfunction "G_2") (pintype "passive"))
      (node (ref "R26") (pin "1") (pinfunction "1_1") (pintype "passive"))
      (node (ref "R7") (pin "2") (pinfunction "2_2") (pintype "passive"))
      (node (ref "TVS1") (pin "3") (pinfunction "ID_3") (pintype "passive"))
      (node (ref "USB") (pin "ID") (pinfunction "4_ID") (pintype "passive"))
    )
    (net (code "66") (name "VBAT") (class "Default")
      (node (ref "BAT") (pin "2") (pinfunction "2_2") (pintype "passive"))
      (node (ref "C28") (pin "2") (pinfunction "2_2") (pintype "passive"))
      (node (ref "IC2") (pin "13") (pinfunction "VBAT_13") (pintype "bidirectional"))
      (node (ref "IC2") (pin "14") (pinfunction "VBAT_14") (pintype "bidirectional"))
    )
    (net (code "67") (name "VCC") (class "Default")
      (node (ref "C2") (pin "2") (pinfunction "2_2") (pintype "passive"))
      (node (ref "C23") (pin "2") (pinfunction "2_2") (pintype "passive"))
      (node (ref "C24") (pin "2") (pinfunction "2_2") (pintype "passive"))
      (node (ref "C25") (pin "2") (pinfunction "2_2") (pintype "passive"))
      (node (ref "C9") (pin "2") (pinfunction "2_2") (pintype "passive"))
      (node (ref "CONN_DATA") (pin "1") (pinfunction "1_1") (pintype "passive"))
      (node (ref "CONN_DATA") (pin "2") (pinfunction "2_2") (pintype "passive"))
      (node (ref "D1") (pin "-") (pinfunction "-_-") (pintype "passive"))
      (node (ref "F1") (pin "2") (pinfunction "2_2") (pintype "passive"))
      (node (ref "F2") (pin "1") (pinfunction "1_1") (pintype "passive"))
      (node (ref "IC5") (pin "17") (pinfunction "VDDIO1_17") (pintype "power_in"))
      (node (ref "IC5") (pin "36") (pinfunction "VDDIO2_36") (pintype "power_in"))
      (node (ref "IC5") (pin "44") (pinfunction "VDDIN_44") (pintype "power_in"))
      (node (ref "IC6") (pin "8") (pinfunction "VCC_8") (pintype "bidirectional"))
      (node (ref "L5") (pin "1") (pinfunction "1_1") (pintype "passive"))
      (node (ref "LED1") (pin "4") (pinfunction "A_4") (pintype "passive"))
      (node (ref "LED2") (pin "A") (pinfunction "A_A") (pintype "passive"))
      (node (ref "LED3") (pin "A") (pinfunction "A_A") (pintype "passive"))
      (node (ref "Q1") (pin "1") (pinfunction "S_1") (pintype "passive"))
      (node (ref "Q1") (pin "4") (pinfunction "S_4") (pintype "passive"))
      (node (ref "R13") (pin "2") (pinfunction "2_2") (pintype "passive"))
      (node (ref "R14") (pin "2") (pinfunction "2_2") (pintype "passive"))
      (node (ref "R16") (pin "2") (pinfunction "2_2") (pintype "passive"))
      (node (ref "R17") (pin "2") (pinfunction "2_2") (pintype "passive"))
      (node (ref "R24") (pin "2") (pinfunction "2_2") (pintype "passive"))
      (node (ref "R25") (pin "2") (pinfunction "2_2") (pintype "passive"))
      (node (ref "R26") (pin "2") (pinfunction "2_2") (pintype "passive"))
      (node (ref "R28") (pin "2") (pinfunction "2_2") (pintype "passive"))
      (node (ref "R30") (pin "2") (pinfunction "2_2") (pintype "passive"))
      (node (ref "R8") (pin "2") (pinfunction "2_2") (pintype "passive"))
      (node (ref "SD1") (pin "4") (pinfunction "VCC_4") (pintype "bidirectional"))
      (node (ref "SWD") (pin "1") (pinfunction "1_1") (pintype "passive"))
    )
    (net (code "68") (name "VCC_GROOVE") (class "Default")
      (node (ref "Q3") (pin "3") (pinfunction "D_3") (pintype "passive"))
      (node (ref "Q3") (pin "6") (pinfunction "D_6") (pintype "passive"))
      (node (ref "Q3") (pin "TP1") (pinfunction "D_TP1") (pintype "passive"))
      (node (ref "Q3") (pin "TP2") (pinfunction "D_TP2") (pintype "passive"))
      (node (ref "R22") (pin "2") (pinfunction "2_2") (pintype "passive"))
      (node (ref "R23") (pin "2") (pinfunction "2_2") (pintype "passive"))
      (node (ref "X1") (pin "3") (pinfunction "3_3") (pintype "bidirectional"))
    )
    (net (code "69") (name "VCC_WIFI") (class "Default")
      (node (ref "C1") (pin "2") (pinfunction "2_2") (pintype "passive"))
      (node (ref "IC4") (pin "1") (pinfunction "RESET_1") (pintype "input"))
      (node (ref "IC4") (pin "17") (pinfunction "GPIO2_17") (pintype "bidirectional"))
      (node (ref "IC4") (pin "8") (pinfunction "VCC_8") (pintype "power_in"))
      (node (ref "L3") (pin "1") (pinfunction "1_1") (pintype "passive"))
      (node (ref "R3") (pin "2") (pinfunction "2_2") (pintype "passive"))
    )
    (net (code "70") (name "VSYS") (class "Default")
      (node (ref "C10") (pin "2") (pinfunction "2_2") (pintype "passive"))
      (node (ref "C11") (pin "2") (pinfunction "2_2") (pintype "passive"))
      (node (ref "C15") (pin "2") (pinfunction "2_2") (pintype "passive"))
      (node (ref "C16") (pin "2") (pinfunction "2_2") (pintype "passive"))
      (node (ref "C18") (pin "2") (pinfunction "2_2") (pintype "passive"))
      (node (ref "IC1") (pin "4") (pinfunction "IN_4") (pintype "bidirectional"))
      (node (ref "IC2") (pin "15") (pinfunction "SYS_15") (pintype "bidirectional"))
      (node (ref "IC2") (pin "16") (pinfunction "SYS_16") (pintype "bidirectional"))
      (node (ref "IC3") (pin "6") (pinfunction "IN_6") (pintype "bidirectional"))
      (node (ref "L2") (pin "2") (pinfunction "2_2") (pintype "bidirectional"))
      (node (ref "L7") (pin "P$1") (pinfunction "P$1_P$1") (pintype "bidirectional"))
      (node (ref "R2") (pin "2") (pinfunction "2_2") (pintype "passive"))
      (node (ref "R5") (pin "1") (pinfunction "1_1") (pintype "passive"))
    )
    (net (code "71") (name "VUSB") (class "Default")
      (node (ref "C4") (pin "2") (pinfunction "2_2") (pintype "passive"))
      (node (ref "C5") (pin "2") (pinfunction "2_2") (pintype "passive"))
      (node (ref "C6") (pin "2") (pinfunction "2_2") (pintype "passive"))
      (node (ref "IC2") (pin "1") (pinfunction "VBUS_1") (pintype "bidirectional"))
      (node (ref "IC2") (pin "24") (pinfunction "VBUS_24") (pintype "bidirectional"))
      (node (ref "L1") (pin "2") (pinfunction "2_2") (pintype "passive"))
    )
    (net (code "72") (name "WIFI_LED") (class "Default")
      (node (ref "IC4") (pin "19") (pinfunction "GPIO5_19") (pintype "bidirectional"))
      (node (ref "R4") (pin "1") (pinfunction "1_1") (pintype "passive"))
    )
    (net (code "73") (name "unconnected-(IC2-QON-Pad12)") (class "Default")
      (node (ref "IC2") (pin "12") (pinfunction "QON_12") (pintype "bidirectional"))
    )
    (net (code "74") (name "unconnected-(IC2-STAT-Pad4)") (class "Default")
      (node (ref "IC2") (pin "4") (pinfunction "STAT_4") (pintype "bidirectional"))
    )
    (net (code "75") (name "unconnected-(IC2-{slash}PG-Pad3)") (class "Default")
      (node (ref "IC2") (pin "3") (pinfunction "/PG_3") (pintype "bidirectional"))
    )
    (net (code "76") (name "unconnected-(IC3-PG-Pad4)") (class "Default")
      (node (ref "IC3") (pin "4") (pinfunction "PG_4") (pintype "bidirectional"))
    )
    (net (code "77") (name "unconnected-(IC4-ADC-Pad2)") (class "Default")
      (node (ref "IC4") (pin "2") (pinfunction "ADC_2") (pintype "passive"))
    )
    (net (code "78") (name "unconnected-(IC4-GPIO9-Pad11)") (class "Default")
      (node (ref "IC4") (pin "11") (pinfunction "GPIO9_11") (pintype "bidirectional"))
    )
    (net (code "79") (name "unconnected-(IC4-GPIO10-Pad12)") (class "Default")
      (node (ref "IC4") (pin "12") (pinfunction "GPIO10_12") (pintype "bidirectional"))
    )
    (net (code "80") (name "unconnected-(IC4-GPIO12-Pad6)") (class "Default")
      (node (ref "IC4") (pin "6") (pinfunction "GPIO12_6") (pintype "bidirectional"))
    )
    (net (code "81") (name "unconnected-(IC4-GPIO13-Pad7)") (class "Default")
      (node (ref "IC4") (pin "7") (pinfunction "GPIO13_7") (pintype "bidirectional"))
    )
    (net (code "82") (name "unconnected-(IC4-GPIO16-Pad4)") (class "Default")
      (node (ref "IC4") (pin "4") (pinfunction "GPIO16_4") (pintype "bidirectional"))
    )
    (net (code "83") (name "unconnected-(IC4-MISO-Pad10)") (class "Default")
      (node (ref "IC4") (pin "10") (pinfunction "MISO_10") (pintype "passive"))
    )
    (net (code "84") (name "unconnected-(IC4-MOSI-Pad13)") (class "Default")
      (node (ref "IC4") (pin "13") (pinfunction "MOSI_13") (pintype "bidirectional"))
    )
    (net (code "85") (name "unconnected-(IC4-SCLK-Pad14)") (class "Default")
      (node (ref "IC4") (pin "14") (pinfunction "SCLK_14") (pintype "bidirectional"))
    )
    (net (code "86") (name "unconnected-(IC6-IO3{slash}RESET#-Pad7)") (class "Default")
      (node (ref "IC6") (pin "7") (pinfunction "IO3/RESET#_7") (pintype "bidirectional"))
    )
    (net (code "87") (name "unconnected-(IC6-WP#{slash}IO2-Pad3)") (class "Default")
      (node (ref "IC6") (pin "3") (pinfunction "WP#/IO2_3") (pintype "bidirectional"))
    )
    (net (code "88") (name "unconnected-(SD1-DAT1-Pad8)") (class "Default")
      (node (ref "SD1") (pin "8") (pinfunction "DAT1_8") (pintype "bidirectional"))
    )
    (net (code "89") (name "unconnected-(SD1-DAT2-Pad1)") (class "Default")
      (node (ref "SD1") (pin "1") (pinfunction "DAT2_1") (pintype "bidirectional"))
    )
    (net (code "90") (name "unconnected-(SWD-Pad6)") (class "Default")
      (node (ref "SWD") (pin "6") (pinfunction "6_6") (pintype "passive"))
    )
    (net (code "91") (name "unconnected-(SWD-Pad7)") (class "Default")
      (node (ref "SWD") (pin "7") (pinfunction "7_7") (pintype "passive"))
    )
    (net (code "92") (name "unconnected-(SWD-Pad8)") (class "Default")
      (node (ref "SWD") (pin "8") (pinfunction "8_8") (pintype "passive"))
    )
    (net (code "93") (name "unconnected-(TVS1-N.C.-Pad5)") (class "Default")
      (node (ref "TVS1") (pin "5") (pinfunction "N.C._5") (pintype "passive"))
    )
    (net (code "94") (name "~{INT_CCS}") (class "Default")
      (node (ref "CONN_DATA") (pin "5") (pinfunction "5_5") (pintype "passive"))
      (node (ref "IC5") (pin "13") (pinfunction "PA8/I2C/AIN16/SCOM2PAD0+/TC0_13") (pintype "bidirectional"))
    )
    (net (code "95") (name "~{WAKE_CCS}") (class "Default")
      (node (ref "CONN_DATA") (pin "7") (pinfunction "7_7") (pintype "passive"))
      (node (ref "IC5") (pin "41") (pinfunction "PA28/EIC_41") (pintype "bidirectional"))
    )
  )
)
